# Sheet2_-_Moteur.net
KiCad netlist of a schematic drawn in Altium Designer
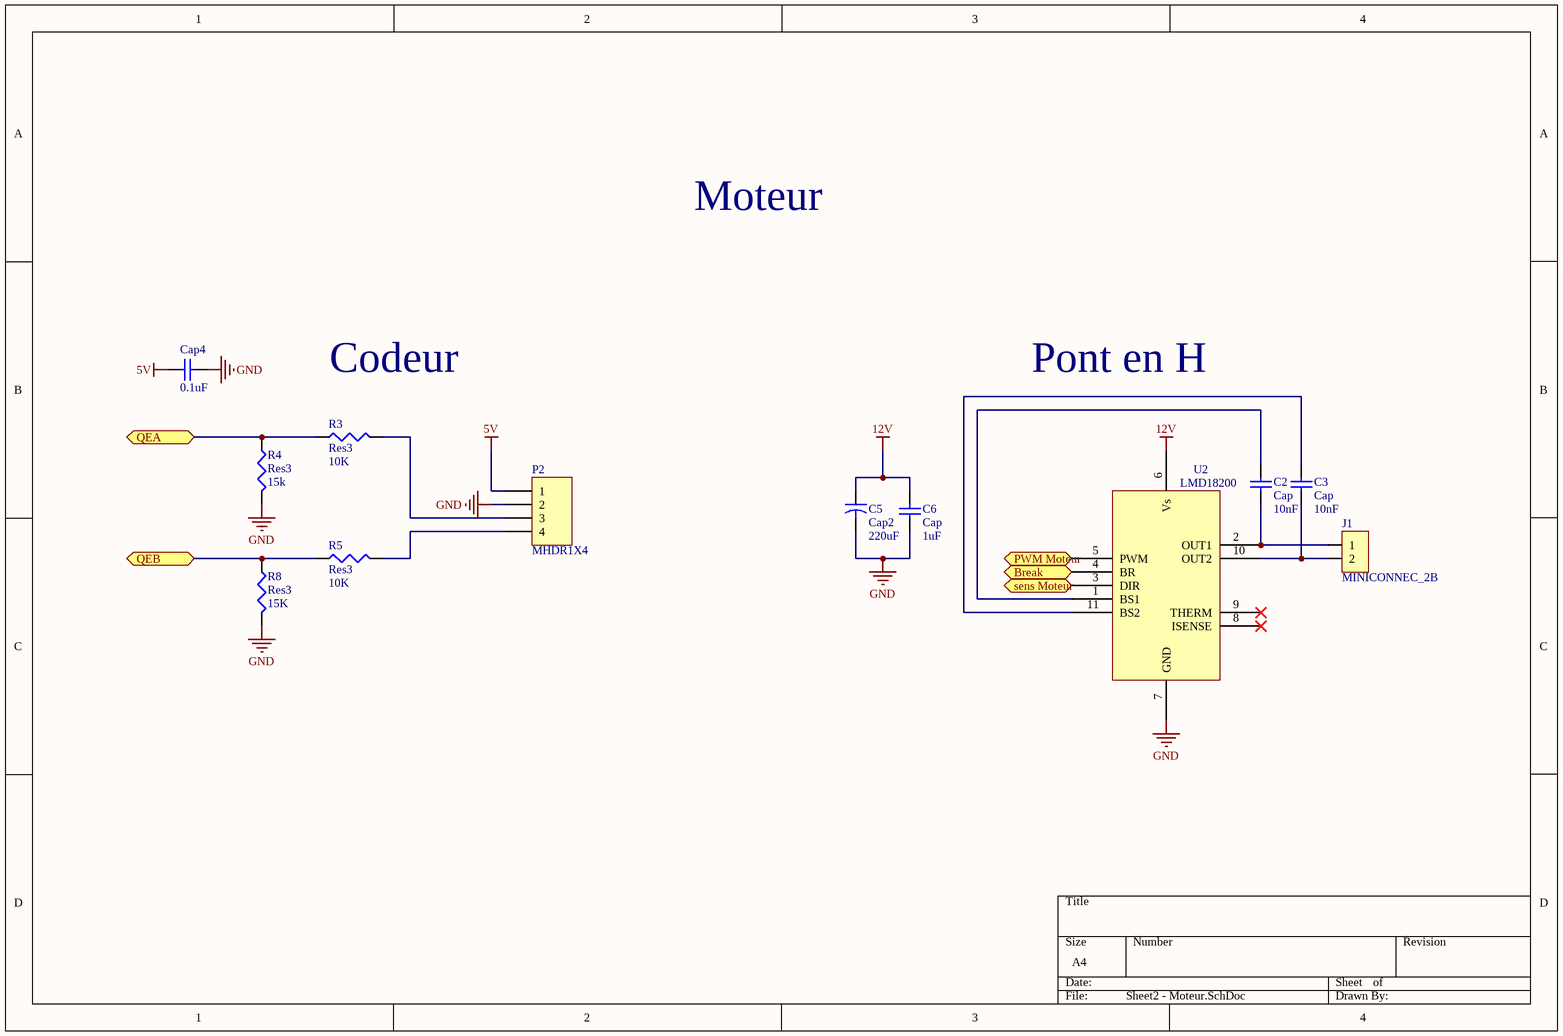
[diagram p0: Sheet2 - Moteur.SchDoc]

(export (version "E")
  (design (tool "Eeschema 10.0.6"))
  (components
    (comp (ref "C2")
      (value "Cap")
      (footprint "RAD-0.3")
      (description "Capacitor")
      (fields (field (name "ALTIUM_VALUE") "10nF") (field (name "PUBLISHER") "Altium Limited"))
      (libsource (lib "Miscellaneous Devices") (part "Cap"))
    )
    (comp (ref "C3")
      (value "Cap")
      (footprint "RAD-0.3")
      (description "Capacitor")
      (fields (field (name "ALTIUM_VALUE") "10nF") (field (name "PUBLISHER") "Altium Limited"))
      (libsource (lib "Miscellaneous Devices") (part "Cap"))
    )
    (comp (ref "C5")
      (value "Cap2")
      (footprint "CAPR5-4X5")
      (description "Capacitor")
      (fields (field (name "ALTIUM_VALUE") "220uF") (field (name "PUBLISHER") "Altium Limited"))
      (libsource (lib "Miscellaneous Devices") (part "Cap2"))
    )
    (comp (ref "C6")
      (value "Cap")
      (footprint "RAD-0.3")
      (description "Capacitor")
      (fields (field (name "ALTIUM_VALUE") "1uF") (field (name "PUBLISHER") "Altium Limited"))
      (libsource (lib "Miscellaneous Devices") (part "Cap"))
    )
    (comp (ref "Cap4")
      (value "0.1uF")
      (footprint "RAD-0.3")
      (description "Capacitor")
      (fields (field (name "PUBLISHER") "Altium Limited"))
      (libsource (lib "Miscellaneous Devices") (part "Cap"))
    )
    (comp (ref "J1")
      (value "MINICONNEC_2B")
      (footprint "MINICONNEC_C")
      (description "Connecteur")
      (libsource (lib "lib_peb_1") (part "MINICONNEC_2B"))
    )
    (comp (ref "P2")
      (value "MHDR1X4")
      (footprint "MHDR1X4")
      (description "Header, 4-Pin")
      (fields (field (name "PUBLISHER") "Altium Limited"))
      (libsource (lib "Miscellaneous Connectors") (part "MHDR1X4"))
    )
    (comp (ref "R3")
      (value "Res3")
      (footprint "RESC1608L")
      (description "Resistor")
      (fields (field (name "ALTIUM_VALUE") "10K") (field (name "PUBLISHER") "Altium Limited"))
      (libsource (lib "Miscellaneous Devices") (part "Res3"))
    )
    (comp (ref "R4")
      (value "Res3")
      (footprint "RESC1608L")
      (description "Resistor")
      (fields (field (name "ALTIUM_VALUE") "15k") (field (name "PUBLISHER") "Altium Limited"))
      (libsource (lib "Miscellaneous Devices") (part "Res3"))
    )
    (comp (ref "R5")
      (value "Res3")
      (footprint "RESC1608L")
      (description "Resistor")
      (fields (field (name "ALTIUM_VALUE") "10K") (field (name "PUBLISHER") "Altium Limited"))
      (libsource (lib "Miscellaneous Devices") (part "Res3"))
    )
    (comp (ref "R8")
      (value "Res3")
      (footprint "RESC1608L")
      (description "Resistor")
      (fields (field (name "ALTIUM_VALUE") "15K") (field (name "PUBLISHER") "Altium Limited"))
      (libsource (lib "Miscellaneous Devices") (part "Res3"))
    )
    (comp (ref "U2")
      (value "LMD18200")
      (footprint "TA11B")
      (description "Pont-H")
      (libsource (lib "lib_peb_1") (part "LMD18200"))
    )
  )
  (nets
    (net (code "1") (name "/Break") (class "Default")
      (node (ref "U2") (pin "4") (pinfunction "BR_4") (pintype "passive"))
    )
    (net (code "2") (name "/PWM Moteur") (class "Default")
      (node (ref "U2") (pin "5") (pinfunction "PWM_5") (pintype "passive"))
    )
    (net (code "3") (name "/QEA") (class "Default")
      (node (ref "R3") (pin "1") (pinfunction "1_1") (pintype "passive"))
      (node (ref "R4") (pin "1") (pinfunction "1_1") (pintype "passive"))
    )
    (net (code "4") (name "/QEB") (class "Default")
      (node (ref "R5") (pin "1") (pinfunction "1_1") (pintype "passive"))
      (node (ref "R8") (pin "1") (pinfunction "1_1") (pintype "passive"))
    )
    (net (code "5") (name "/sens Moteur") (class "Default")
      (node (ref "U2") (pin "3") (pinfunction "DIR_3") (pintype "passive"))
    )
    (net (code "6") (name "5V") (class "Default")
      (node (ref "Cap4") (pin "2") (pinfunction "2_2") (pintype "passive"))
      (node (ref "P2") (pin "1") (pinfunction "1_1") (pintype "passive"))
    )
    (net (code "7") (name "12V") (class "Default")
      (node (ref "C5") (pin "1") (pinfunction "1_1") (pintype "passive"))
      (node (ref "C6") (pin "2") (pinfunction "2_2") (pintype "passive"))
      (node (ref "U2") (pin "6") (pinfunction "Vs_6") (pintype "power_in"))
    )
    (net (code "8") (name "GND") (class "Default")
      (node (ref "C5") (pin "2") (pinfunction "2_2") (pintype "passive"))
      (node (ref "C6") (pin "1") (pinfunction "1_1") (pintype "passive"))
      (node (ref "Cap4") (pin "1") (pinfunction "1_1") (pintype "passive"))
      (node (ref "P2") (pin "2") (pinfunction "2_2") (pintype "passive"))
      (node (ref "R4") (pin "2") (pinfunction "2_2") (pintype "passive"))
      (node (ref "R8") (pin "2") (pinfunction "2_2") (pintype "passive"))
      (node (ref "U2") (pin "7") (pinfunction "GND_7") (pintype "power_in"))
    )
    (net (code "9") (name "Net-(P2-Pad3)") (class "Default")
      (node (ref "P2") (pin "3") (pinfunction "3_3") (pintype "passive"))
      (node (ref "R3") (pin "2") (pinfunction "2_2") (pintype "passive"))
    )
    (net (code "10") (name "Net-(P2-Pad4)") (class "Default")
      (node (ref "P2") (pin "4") (pinfunction "4_4") (pintype "passive"))
      (node (ref "R5") (pin "2") (pinfunction "2_2") (pintype "passive"))
    )
    (net (code "11") (name "Net-(U2-BS1)") (class "Default")
      (node (ref "C2") (pin "1") (pinfunction "1_1") (pintype "passive"))
      (node (ref "U2") (pin "1") (pinfunction "BS1_1") (pintype "passive"))
    )
    (net (code "12") (name "Net-(U2-BS2)") (class "Default")
      (node (ref "C3") (pin "1") (pinfunction "1_1") (pintype "passive"))
      (node (ref "U2") (pin "11") (pinfunction "BS2_11") (pintype "passive"))
    )
    (net (code "13") (name "Net-(U2-OUT1)") (class "Default")
      (node (ref "C2") (pin "2") (pinfunction "2_2") (pintype "passive"))
      (node (ref "J1") (pin "1") (pinfunction "1_1") (pintype "passive"))
      (node (ref "U2") (pin "2") (pinfunction "OUT1_2") (pintype "passive"))
    )
    (net (code "14") (name "Net-(U2-OUT2)") (class "Default")
      (node (ref "C3") (pin "2") (pinfunction "2_2") (pintype "passive"))
      (node (ref "J1") (pin "2") (pinfunction "2_2") (pintype "passive"))
      (node (ref "U2") (pin "10") (pinfunction "OUT2_10") (pintype "passive"))
    )
    (net (code "15") (name "unconnected-(U2-ISENSE-Pad8)") (class "Default")
      (node (ref "U2") (pin "8") (pinfunction "ISENSE_8") (pintype "passive+no_connect"))
    )
    (net (code "16") (name "unconnected-(U2-THERM-Pad9)") (class "Default")
      (node (ref "U2") (pin "9") (pinfunction "THERM_9") (pintype "passive+no_connect"))
    )
  )
)
